# handlauf.net
KiCad netlist of a schematic drawn in EAGLE
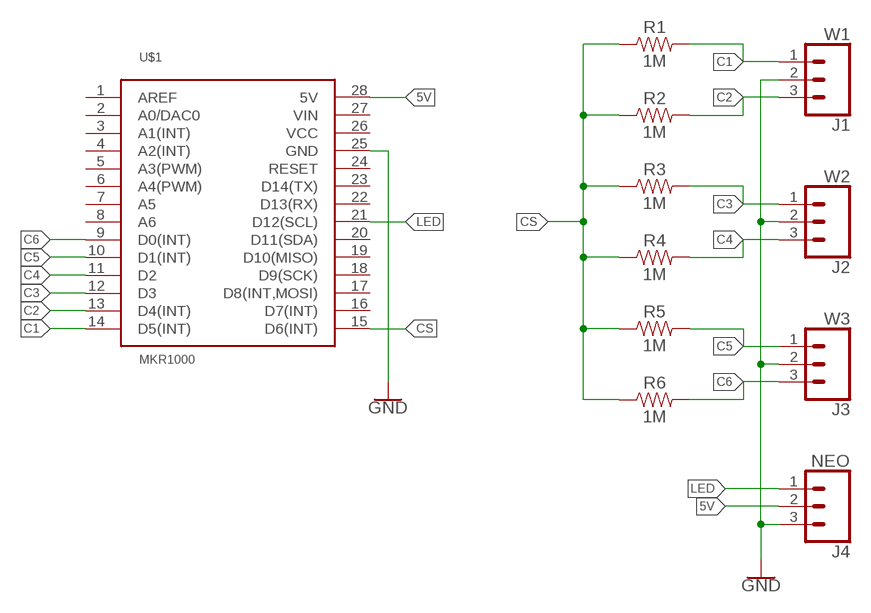
[diagram p0: schematic, sheet 1]

(export (version "E")
  (design (tool "Eeschema 10.0.6"))
  (components
    (comp (ref "J1")
      (value "W1")
      (footprint "eagle-import:SCREWTERMINAL-3.5MM-3")
      (libsource (lib "eagle-import") (part "CONN_03SCREW"))
    )
    (comp (ref "J2")
      (value "W2")
      (footprint "eagle-import:SCREWTERMINAL-3.5MM-3")
      (libsource (lib "eagle-import") (part "CONN_03SCREW"))
    )
    (comp (ref "J3")
      (value "W3")
      (footprint "eagle-import:SCREWTERMINAL-3.5MM-3")
      (libsource (lib "eagle-import") (part "CONN_03SCREW"))
    )
    (comp (ref "J4")
      (value "NEO")
      (footprint "eagle-import:1X03")
      (libsource (lib "eagle-import") (part "CONN_03"))
    )
    (comp (ref "R1")
      (value "1M")
      (footprint "eagle-import:AXIAL-0.3")
      (libsource (lib "eagle-import") (part "RESISTORAXIAL-0.3"))
    )
    (comp (ref "R2")
      (value "1M")
      (footprint "eagle-import:AXIAL-0.3")
      (libsource (lib "eagle-import") (part "RESISTORAXIAL-0.3"))
    )
    (comp (ref "R3")
      (value "1M")
      (footprint "eagle-import:AXIAL-0.3")
      (libsource (lib "eagle-import") (part "RESISTORAXIAL-0.3"))
    )
    (comp (ref "R4")
      (value "1M")
      (footprint "eagle-import:AXIAL-0.3")
      (libsource (lib "eagle-import") (part "RESISTORAXIAL-0.3"))
    )
    (comp (ref "R5")
      (value "1M")
      (footprint "eagle-import:AXIAL-0.3")
      (libsource (lib "eagle-import") (part "RESISTORAXIAL-0.3"))
    )
    (comp (ref "R6")
      (value "1M")
      (footprint "eagle-import:AXIAL-0.3")
      (libsource (lib "eagle-import") (part "RESISTORAXIAL-0.3"))
    )
    (comp (ref "U$1")
      (value "MKR1000")
      (footprint "eagle-import:MKR1000-SOCKET")
      (libsource (lib "eagle-import") (part "MKR1000"))
    )
  )
  (nets
    (net (code "1") (name "5V") (class "Default")
      (node (ref "J4") (pin "2") (pinfunction "2_2") (pintype "passive"))
      (node (ref "U$1") (pin "28") (pinfunction "5V_28") (pintype "bidirectional"))
    )
    (net (code "2") (name "C1") (class "Default")
      (node (ref "J1") (pin "1") (pinfunction "1_1") (pintype "passive"))
      (node (ref "R1") (pin "P$2") (pinfunction "2_P$2") (pintype "passive"))
      (node (ref "U$1") (pin "14") (pinfunction "D5(INT)_14") (pintype "bidirectional"))
    )
    (net (code "3") (name "C2") (class "Default")
      (node (ref "J1") (pin "3") (pinfunction "3_3") (pintype "passive"))
      (node (ref "R2") (pin "P$2") (pinfunction "2_P$2") (pintype "passive"))
      (node (ref "U$1") (pin "13") (pinfunction "D4(INT)_13") (pintype "bidirectional"))
    )
    (net (code "4") (name "C3") (class "Default")
      (node (ref "J2") (pin "1") (pinfunction "1_1") (pintype "passive"))
      (node (ref "R3") (pin "P$2") (pinfunction "2_P$2") (pintype "passive"))
      (node (ref "U$1") (pin "12") (pinfunction "D3_12") (pintype "bidirectional"))
    )
    (net (code "5") (name "C4") (class "Default")
      (node (ref "J2") (pin "3") (pinfunction "3_3") (pintype "passive"))
      (node (ref "R4") (pin "P$2") (pinfunction "2_P$2") (pintype "passive"))
      (node (ref "U$1") (pin "11") (pinfunction "D2_11") (pintype "bidirectional"))
    )
    (net (code "6") (name "C5") (class "Default")
      (node (ref "J3") (pin "1") (pinfunction "1_1") (pintype "passive"))
      (node (ref "R5") (pin "P$2") (pinfunction "2_P$2") (pintype "passive"))
      (node (ref "U$1") (pin "10") (pinfunction "D1(INT)_10") (pintype "bidirectional"))
    )
    (net (code "7") (name "C6") (class "Default")
      (node (ref "J3") (pin "3") (pinfunction "3_3") (pintype "passive"))
      (node (ref "R6") (pin "P$2") (pinfunction "2_P$2") (pintype "passive"))
      (node (ref "U$1") (pin "9") (pinfunction "D0(INT)_9") (pintype "bidirectional"))
    )
    (net (code "8") (name "CS") (class "Default")
      (node (ref "R1") (pin "P$1") (pinfunction "1_P$1") (pintype "passive"))
      (node (ref "R2") (pin "P$1") (pinfunction "1_P$1") (pintype "passive"))
      (node (ref "R3") (pin "P$1") (pinfunction "1_P$1") (pintype "passive"))
      (node (ref "R4") (pin "P$1") (pinfunction "1_P$1") (pintype "passive"))
      (node (ref "R5") (pin "P$1") (pinfunction "1_P$1") (pintype "passive"))
      (node (ref "R6") (pin "P$1") (pinfunction "1_P$1") (pintype "passive"))
      (node (ref "U$1") (pin "15") (pinfunction "D6(INT)_15") (pintype "bidirectional"))
    )
    (net (code "9") (name "GND") (class "Default")
      (node (ref "J1") (pin "2") (pinfunction "2_2") (pintype "passive"))
      (node (ref "J2") (pin "2") (pinfunction "2_2") (pintype "passive"))
      (node (ref "J3") (pin "2") (pinfunction "2_2") (pintype "passive"))
      (node (ref "J4") (pin "3") (pinfunction "3_3") (pintype "passive"))
      (node (ref "U$1") (pin "25") (pinfunction "GND_25") (pintype "bidirectional"))
    )
    (net (code "10") (name "LED") (class "Default")
      (node (ref "J4") (pin "1") (pinfunction "1_1") (pintype "passive"))
      (node (ref "U$1") (pin "21") (pinfunction "D12(SCL)_21") (pintype "bidirectional"))
    )
    (net (code "11") (name "unconnected-(U$1-A0{slash}DAC0-Pad2)") (class "Default")
      (node (ref "U$1") (pin "2") (pinfunction "A0/DAC0_2") (pintype "bidirectional"))
    )
    (net (code "12") (name "unconnected-(U$1-A1(INT)-Pad3)") (class "Default")
      (node (ref "U$1") (pin "3") (pinfunction "A1(INT)_3") (pintype "bidirectional"))
    )
    (net (code "13") (name "unconnected-(U$1-A2(INT)-Pad4)") (class "Default")
      (node (ref "U$1") (pin "4") (pinfunction "A2(INT)_4") (pintype "bidirectional"))
    )
    (net (code "14") (name "unconnected-(U$1-A3(PWM)-Pad5)") (class "Default")
      (node (ref "U$1") (pin "5") (pinfunction "A3(PWM)_5") (pintype "bidirectional"))
    )
    (net (code "15") (name "unconnected-(U$1-A4(PWM)-Pad6)") (class "Default")
      (node (ref "U$1") (pin "6") (pinfunction "A4(PWM)_6") (pintype "bidirectional"))
    )
    (net (code "16") (name "unconnected-(U$1-A5-Pad7)") (class "Default")
      (node (ref "U$1") (pin "7") (pinfunction "A5_7") (pintype "bidirectional"))
    )
    (net (code "17") (name "unconnected-(U$1-A6-Pad8)") (class "Default")
      (node (ref "U$1") (pin "8") (pinfunction "A6_8") (pintype "bidirectional"))
    )
    (net (code "18") (name "unconnected-(U$1-AREF-Pad1)") (class "Default")
      (node (ref "U$1") (pin "1") (pinfunction "AREF_1") (pintype "bidirectional"))
    )
    (net (code "19") (name "unconnected-(U$1-D7(INT)-Pad16)") (class "Default")
      (node (ref "U$1") (pin "16") (pinfunction "D7(INT)_16") (pintype "bidirectional"))
    )
    (net (code "20") (name "unconnected-(U$1-D8(INT,MOSI)-Pad17)") (class "Default")
      (node (ref "U$1") (pin "17") (pinfunction "D8(INT,MOSI)_17") (pintype "bidirectional"))
    )
    (net (code "21") (name "unconnected-(U$1-D9(SCK)-Pad18)") (class "Default")
      (node (ref "U$1") (pin "18") (pinfunction "D9(SCK)_18") (pintype "bidirectional"))
    )
    (net (code "22") (name "unconnected-(U$1-D10(MISO)-Pad19)") (class "Default")
      (node (ref "U$1") (pin "19") (pinfunction "D10(MISO)_19") (pintype "bidirectional"))
    )
    (net (code "23") (name "unconnected-(U$1-D11(SDA)-Pad20)") (class "Default")
      (node (ref "U$1") (pin "20") (pinfunction "D11(SDA)_20") (pintype "bidirectional"))
    )
    (net (code "24") (name "unconnected-(U$1-D13(RX)-Pad22)") (class "Default")
      (node (ref "U$1") (pin "22") (pinfunction "D13(RX)_22") (pintype "bidirectional"))
    )
    (net (code "25") (name "unconnected-(U$1-D14(TX)-Pad23)") (class "Default")
      (node (ref "U$1") (pin "23") (pinfunction "D14(TX)_23") (pintype "bidirectional"))
    )
    (net (code "26") (name "unconnected-(U$1-RESET-Pad24)") (class "Default")
      (node (ref "U$1") (pin "24") (pinfunction "RESET_24") (pintype "bidirectional"))
    )
    (net (code "27") (name "unconnected-(U$1-VCC-Pad26)") (class "Default")
      (node (ref "U$1") (pin "26") (pinfunction "VCC_26") (pintype "bidirectional"))
    )
    (net (code "28") (name "unconnected-(U$1-VIN-Pad27)") (class "Default")
      (node (ref "U$1") (pin "27") (pinfunction "VIN_27") (pintype "bidirectional"))
    )
  )
)
